# crown-face.net
KiCad netlist of a schematic drawn in EAGLE
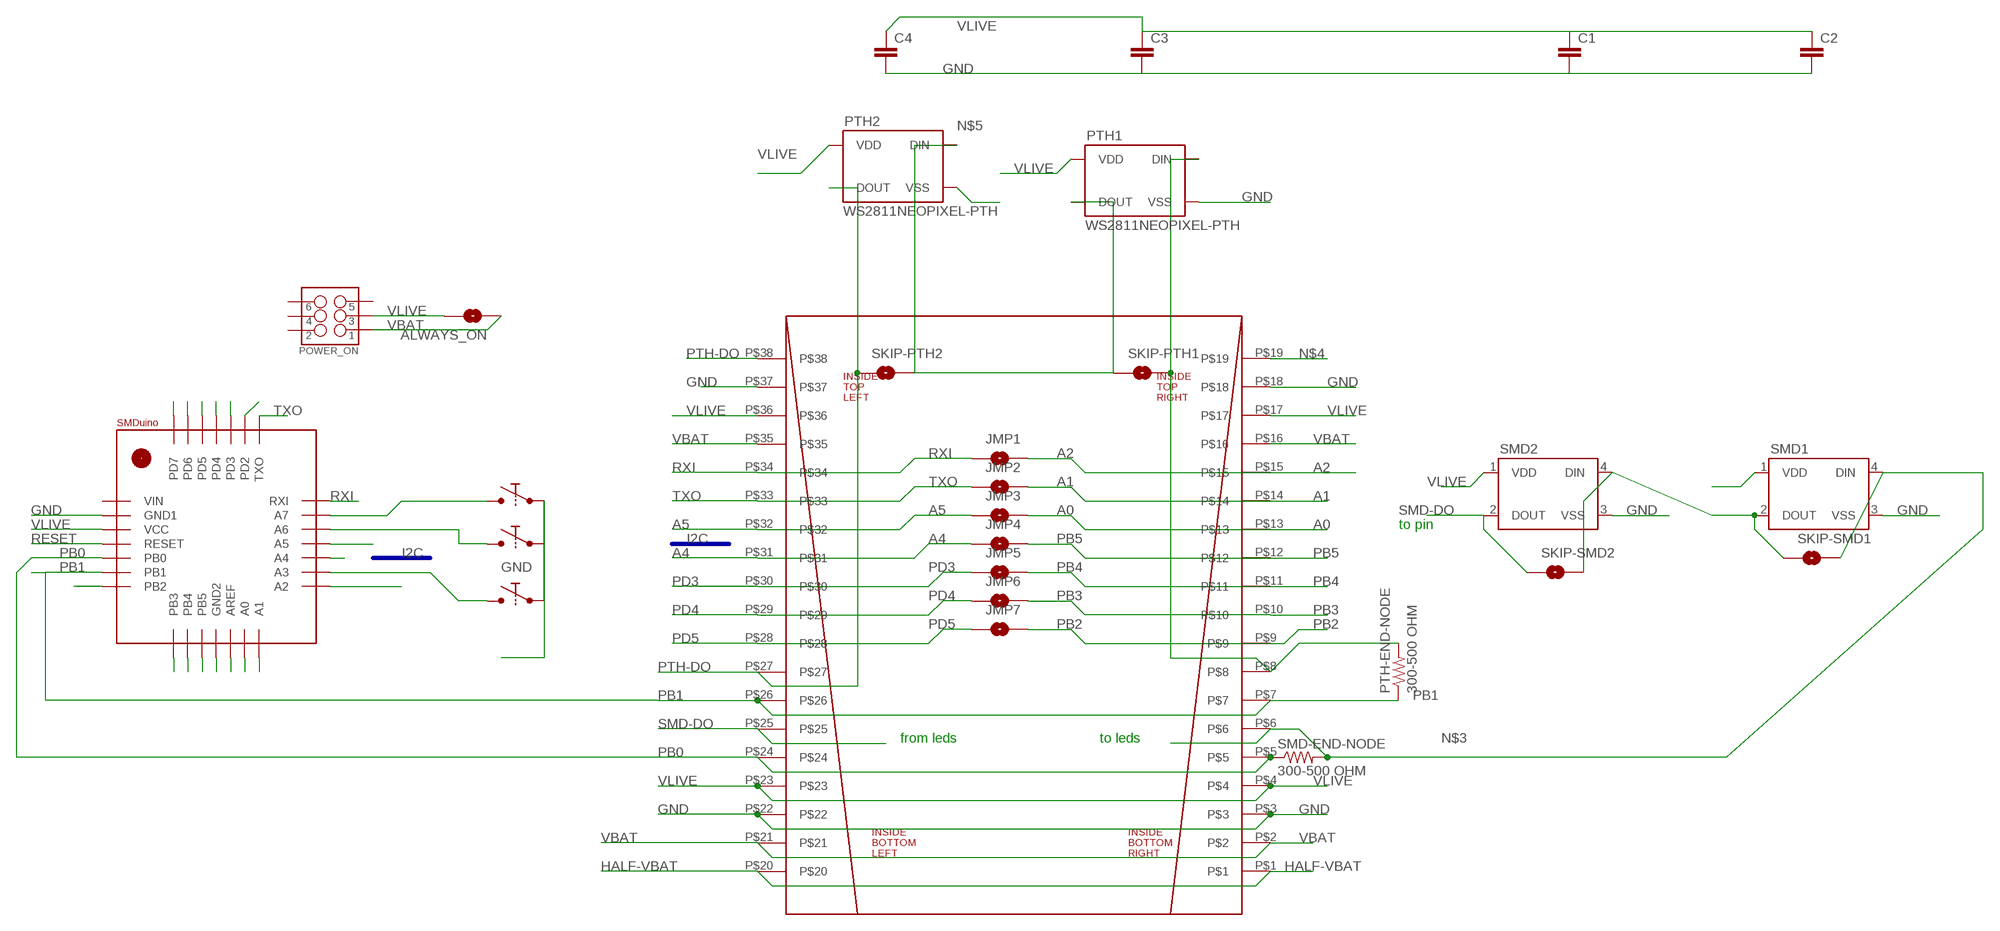
[diagram p0: schematic, sheet 1]

(export (version "E")
  (design (tool "Eeschema 10.0.6"))
  (components
    (comp (ref "A6")
      (value "BUTTONSMD_BUTTON")
      (footprint "eagle-import:SMD_BUTTON")
      (libsource (lib "eagle-import") (part "BUTTONSMD_BUTTON"))
    )
    (comp (ref "A7")
      (value "BUTTONSMD_BUTTON")
      (footprint "eagle-import:SMD_BUTTON")
      (libsource (lib "eagle-import") (part "BUTTONSMD_BUTTON"))
    )
    (comp (ref "ALWAYS_ON")
      (value "SOLDERJUMPERNC2")
      (footprint "eagle-import:SJ_2S-NOTRACE")
      (libsource (lib "eagle-import") (part "SOLDERJUMPERNC2"))
    )
    (comp (ref "C1")
      (value "CAP0805")
      (footprint "eagle-import:0805")
      (libsource (lib "eagle-import") (part "CAP0805"))
    )
    (comp (ref "C2")
      (value "CAP0805")
      (footprint "eagle-import:0805")
      (libsource (lib "eagle-import") (part "CAP0805"))
    )
    (comp (ref "C3")
      (value "CAP0805")
      (footprint "eagle-import:0805")
      (libsource (lib "eagle-import") (part "CAP0805"))
    )
    (comp (ref "C4")
      (value "CAP0805")
      (footprint "eagle-import:0805")
      (libsource (lib "eagle-import") (part "CAP0805"))
    )
    (comp (ref "D2")
      (value "BUTTONSMD_BUTTON")
      (footprint "eagle-import:SMD_BUTTON")
      (libsource (lib "eagle-import") (part "BUTTONSMD_BUTTON"))
    )
    (comp (ref "JMP1")
      (value "SOLDERJUMPERNC2")
      (footprint "eagle-import:SJ_2S-NOTRACE")
      (libsource (lib "eagle-import") (part "SOLDERJUMPERNC2"))
    )
    (comp (ref "JMP2")
      (value "SOLDERJUMPERNC2")
      (footprint "eagle-import:SJ_2S-NOTRACE")
      (libsource (lib "eagle-import") (part "SOLDERJUMPERNC2"))
    )
    (comp (ref "JMP3")
      (value "SOLDERJUMPERNC2")
      (footprint "eagle-import:SJ_2S-NOTRACE")
      (libsource (lib "eagle-import") (part "SOLDERJUMPERNC2"))
    )
    (comp (ref "JMP4")
      (value "SOLDERJUMPERNC2")
      (footprint "eagle-import:SJ_2S-NOTRACE")
      (libsource (lib "eagle-import") (part "SOLDERJUMPERNC2"))
    )
    (comp (ref "JMP5")
      (value "SOLDERJUMPERNC2")
      (footprint "eagle-import:SJ_2S-NOTRACE")
      (libsource (lib "eagle-import") (part "SOLDERJUMPERNC2"))
    )
    (comp (ref "JMP6")
      (value "SOLDERJUMPERNC2")
      (footprint "eagle-import:SJ_2S-NOTRACE")
      (libsource (lib "eagle-import") (part "SOLDERJUMPERNC2"))
    )
    (comp (ref "JMP7")
      (value "SOLDERJUMPERNC2")
      (footprint "eagle-import:SJ_2S-NOTRACE")
      (libsource (lib "eagle-import") (part "SOLDERJUMPERNC2"))
    )
    (comp (ref "POWER_ON")
      (value "M03X2FEMALE_SMD")
      (footprint "eagle-import:2X3_SMD")
      (libsource (lib "eagle-import") (part "M03X2FEMALE_SMD"))
    )
    (comp (ref "PTH-END-NODE")
      (value "300-500 OHM")
      (footprint "eagle-import:0805")
      (libsource (lib "eagle-import") (part "RESISTOR0805-RES"))
    )
    (comp (ref "PTH1")
      (value "WS2811NEOPIXEL-PTH")
      (footprint "eagle-import:WS2811-PTH-FLAT")
      (libsource (lib "eagle-import") (part "WS2811NEOPIXEL-PTH"))
    )
    (comp (ref "PTH2")
      (value "WS2811NEOPIXEL-PTH")
      (footprint "eagle-import:WS2811-PTH-FLAT")
      (libsource (lib "eagle-import") (part "WS2811NEOPIXEL-PTH"))
    )
    (comp (ref "SKIP-PTH1")
      (value "SOLDERJUMPERNC2")
      (footprint "eagle-import:SJ_2S-NOTRACE")
      (libsource (lib "eagle-import") (part "SOLDERJUMPERNC2"))
    )
    (comp (ref "SKIP-PTH2")
      (value "SOLDERJUMPERNC2")
      (footprint "eagle-import:SJ_2S-NOTRACE")
      (libsource (lib "eagle-import") (part "SOLDERJUMPERNC2"))
    )
    (comp (ref "SKIP-SMD1")
      (value "SOLDERJUMPERNC2")
      (footprint "eagle-import:SJ_2S-NOTRACE")
      (libsource (lib "eagle-import") (part "SOLDERJUMPERNC2"))
    )
    (comp (ref "SKIP-SMD2")
      (value "SOLDERJUMPERNC2")
      (footprint "eagle-import:SJ_2S-NOTRACE")
      (libsource (lib "eagle-import") (part "SOLDERJUMPERNC2"))
    )
    (comp (ref "SMD-END-NODE")
      (value "300-500 OHM")
      (footprint "eagle-import:0805")
      (libsource (lib "eagle-import") (part "RESISTOR0805-RES"))
    )
    (comp (ref "SMD1")
      (value "WS2812B")
      (footprint "eagle-import:WS2812B")
      (libsource (lib "eagle-import") (part "WS2812B"))
    )
    (comp (ref "SMD2")
      (value "WS2812B")
      (footprint "eagle-import:WS2812B")
      (libsource (lib "eagle-import") (part "WS2812B"))
    )
    (comp (ref "U$1")
      (value "SMDUINO")
      (footprint "eagle-import:SMDUINO")
      (libsource (lib "eagle-import") (part "SMDUINO"))
    )
    (comp (ref "U$2")
      (value "CROWNSTANDARD")
      (footprint "eagle-import:CROWN")
      (libsource (lib "eagle-import") (part "CROWNSTANDARD"))
    )
  )
  (nets
    (net (code "2") (name "/A0") (class "Default")
      (node (ref "JMP3") (pin "2") (pinfunction "2_2") (pintype "passive"))
      (node (ref "U$1") (pin "A0") (pinfunction "A0_A0") (pintype "bidirectional"))
      (node (ref "U$2") (pin "P$13") (pinfunction "P$13_P$13") (pintype "bidirectional"))
    )
    (net (code "3") (name "/A1") (class "Default")
      (node (ref "JMP2") (pin "2") (pinfunction "2_2") (pintype "passive"))
      (node (ref "U$1") (pin "A1") (pinfunction "A1_A1") (pintype "bidirectional"))
      (node (ref "U$2") (pin "P$14") (pinfunction "P$14_P$14") (pintype "bidirectional"))
    )
    (net (code "4") (name "/A2") (class "Default")
      (node (ref "JMP1") (pin "2") (pinfunction "2_2") (pintype "passive"))
      (node (ref "U$1") (pin "A2") (pinfunction "A2_A2") (pintype "bidirectional"))
      (node (ref "U$2") (pin "P$15") (pinfunction "P$15_P$15") (pintype "bidirectional"))
    )
    (net (code "5") (name "/A4") (class "Default")
      (node (ref "JMP4") (pin "1") (pinfunction "1_1") (pintype "passive"))
      (node (ref "U$1") (pin "A4") (pinfunction "A4_A4") (pintype "bidirectional"))
      (node (ref "U$2") (pin "P$31") (pinfunction "P$31_P$31") (pintype "bidirectional"))
    )
    (net (code "6") (name "/A5") (class "Default")
      (node (ref "JMP3") (pin "1") (pinfunction "1_1") (pintype "passive"))
      (node (ref "U$1") (pin "A5") (pinfunction "A5_A5") (pintype "bidirectional"))
      (node (ref "U$2") (pin "P$32") (pinfunction "P$32_P$32") (pintype "bidirectional"))
    )
    (net (code "7") (name "/GND") (class "Default")
      (node (ref "A6") (pin "P$3") (pinfunction "P$2_P$3") (pintype "bidirectional"))
      (node (ref "A6") (pin "P$4") (pinfunction "P$2_P$4") (pintype "bidirectional"))
      (node (ref "A7") (pin "P$3") (pinfunction "P$2_P$3") (pintype "bidirectional"))
      (node (ref "A7") (pin "P$4") (pinfunction "P$2_P$4") (pintype "bidirectional"))
      (node (ref "C1") (pin "2") (pinfunction "2_2") (pintype "passive"))
      (node (ref "C2") (pin "2") (pinfunction "2_2") (pintype "passive"))
      (node (ref "C3") (pin "2") (pinfunction "2_2") (pintype "passive"))
      (node (ref "C4") (pin "2") (pinfunction "2_2") (pintype "passive"))
      (node (ref "D2") (pin "P$3") (pinfunction "P$2_P$3") (pintype "bidirectional"))
      (node (ref "D2") (pin "P$4") (pinfunction "P$2_P$4") (pintype "bidirectional"))
      (node (ref "PTH1") (pin "P$2") (pinfunction "VSS_P$2") (pintype "power_in"))
      (node (ref "PTH1") (pin "P$6") (pinfunction "VSS_P$6") (pintype "power_in"))
      (node (ref "PTH2") (pin "P$2") (pinfunction "VSS_P$2") (pintype "power_in"))
      (node (ref "PTH2") (pin "P$6") (pinfunction "VSS_P$6") (pintype "power_in"))
      (node (ref "SMD1") (pin "3") (pinfunction "VSS_3") (pintype "power_in"))
      (node (ref "SMD2") (pin "3") (pinfunction "VSS_3") (pintype "power_in"))
      (node (ref "U$1") (pin "GND1") (pinfunction "GND1_GND1") (pintype "bidirectional"))
      (node (ref "U$2") (pin "P$18") (pinfunction "P$18_P$18") (pintype "bidirectional"))
      (node (ref "U$2") (pin "P$22") (pinfunction "P$22_P$22") (pintype "bidirectional"))
      (node (ref "U$2") (pin "P$3") (pinfunction "P$3_P$3") (pintype "bidirectional"))
      (node (ref "U$2") (pin "P$37") (pinfunction "P$37_P$37") (pintype "bidirectional"))
    )
    (net (code "8") (name "/HALF-VBAT") (class "Default")
      (node (ref "U$2") (pin "P$1") (pinfunction "P$1_P$1") (pintype "bidirectional"))
      (node (ref "U$2") (pin "P$20") (pinfunction "P$20_P$20") (pintype "bidirectional"))
    )
    (net (code "9") (name "/N$3") (class "Default")
      (node (ref "SKIP-SMD1") (pin "2") (pinfunction "2_2") (pintype "passive"))
      (node (ref "SMD-END-NODE") (pin "2") (pinfunction "2_2") (pintype "passive"))
      (node (ref "SMD1") (pin "4") (pinfunction "DIN_4") (pintype "input"))
      (node (ref "U$2") (pin "P$6") (pinfunction "P$6_P$6") (pintype "bidirectional"))
    )
    (net (code "10") (name "/N$4") (class "Default")
      (node (ref "PTH-END-NODE") (pin "2") (pinfunction "2_2") (pintype "passive"))
      (node (ref "PTH1") (pin "P$4") (pinfunction "DIN_P$4") (pintype "input"))
      (node (ref "PTH1") (pin "P$8") (pinfunction "DIN_P$8") (pintype "input"))
      (node (ref "SKIP-PTH1") (pin "2") (pinfunction "2_2") (pintype "passive"))
      (node (ref "U$2") (pin "P$19") (pinfunction "P$19_P$19") (pintype "bidirectional"))
      (node (ref "U$2") (pin "P$8") (pinfunction "P$8_P$8") (pintype "bidirectional"))
    )
    (net (code "11") (name "/N$5") (class "Default")
      (node (ref "PTH1") (pin "P$1") (pinfunction "DOUT_P$1") (pintype "output"))
      (node (ref "PTH1") (pin "P$5") (pinfunction "DOUT_P$5") (pintype "output"))
      (node (ref "PTH2") (pin "P$4") (pinfunction "DIN_P$4") (pintype "input"))
      (node (ref "PTH2") (pin "P$8") (pinfunction "DIN_P$8") (pintype "input"))
      (node (ref "SKIP-PTH1") (pin "1") (pinfunction "1_1") (pintype "passive"))
      (node (ref "SKIP-PTH2") (pin "2") (pinfunction "2_2") (pintype "passive"))
    )
    (net (code "12") (name "/PB0") (class "Default")
      (node (ref "SMD-END-NODE") (pin "1") (pinfunction "1_1") (pintype "passive"))
      (node (ref "U$1") (pin "PB0") (pinfunction "PB0_PB0") (pintype "bidirectional"))
      (node (ref "U$2") (pin "P$24") (pinfunction "P$24_P$24") (pintype "bidirectional"))
      (node (ref "U$2") (pin "P$5") (pinfunction "P$5_P$5") (pintype "bidirectional"))
    )
    (net (code "13") (name "/PB1") (class "Default")
      (node (ref "PTH-END-NODE") (pin "1") (pinfunction "1_1") (pintype "passive"))
      (node (ref "U$1") (pin "PB1") (pinfunction "PB1_PB1") (pintype "bidirectional"))
      (node (ref "U$2") (pin "P$26") (pinfunction "P$26_P$26") (pintype "bidirectional"))
      (node (ref "U$2") (pin "P$7") (pinfunction "P$7_P$7") (pintype "bidirectional"))
    )
    (net (code "14") (name "/PB2") (class "Default")
      (node (ref "JMP7") (pin "2") (pinfunction "2_2") (pintype "passive"))
      (node (ref "U$1") (pin "PB2") (pinfunction "PB2_PB2") (pintype "bidirectional"))
      (node (ref "U$2") (pin "P$9") (pinfunction "P$9_P$9") (pintype "bidirectional"))
    )
    (net (code "15") (name "/PB3") (class "Default")
      (node (ref "JMP6") (pin "2") (pinfunction "2_2") (pintype "passive"))
      (node (ref "U$1") (pin "PB3") (pinfunction "PB3_PB3") (pintype "bidirectional"))
      (node (ref "U$2") (pin "P$10") (pinfunction "P$10_P$10") (pintype "bidirectional"))
    )
    (net (code "16") (name "/PB4") (class "Default")
      (node (ref "JMP5") (pin "2") (pinfunction "2_2") (pintype "passive"))
      (node (ref "U$1") (pin "PB4") (pinfunction "PB4_PB4") (pintype "bidirectional"))
      (node (ref "U$2") (pin "P$11") (pinfunction "P$11_P$11") (pintype "bidirectional"))
    )
    (net (code "17") (name "/PB5") (class "Default")
      (node (ref "JMP4") (pin "2") (pinfunction "2_2") (pintype "passive"))
      (node (ref "U$1") (pin "PB5") (pinfunction "PB5_PB5") (pintype "bidirectional"))
      (node (ref "U$2") (pin "P$12") (pinfunction "P$12_P$12") (pintype "bidirectional"))
    )
    (net (code "18") (name "/PD3") (class "Default")
      (node (ref "JMP5") (pin "1") (pinfunction "1_1") (pintype "passive"))
      (node (ref "U$1") (pin "PD3") (pinfunction "PD3_PD3") (pintype "bidirectional"))
      (node (ref "U$2") (pin "P$30") (pinfunction "P$30_P$30") (pintype "bidirectional"))
    )
    (net (code "19") (name "/PD4") (class "Default")
      (node (ref "JMP6") (pin "1") (pinfunction "1_1") (pintype "passive"))
      (node (ref "U$1") (pin "PD4") (pinfunction "PD4_PD4") (pintype "bidirectional"))
      (node (ref "U$2") (pin "P$29") (pinfunction "P$29_P$29") (pintype "bidirectional"))
    )
    (net (code "20") (name "/PD5") (class "Default")
      (node (ref "JMP7") (pin "1") (pinfunction "1_1") (pintype "passive"))
      (node (ref "U$1") (pin "PD5") (pinfunction "PD5_PD5") (pintype "bidirectional"))
      (node (ref "U$2") (pin "P$28") (pinfunction "P$28_P$28") (pintype "bidirectional"))
    )
    (net (code "21") (name "/PTH-DO") (class "Default")
      (node (ref "PTH2") (pin "P$1") (pinfunction "DOUT_P$1") (pintype "output"))
      (node (ref "PTH2") (pin "P$5") (pinfunction "DOUT_P$5") (pintype "output"))
      (node (ref "SKIP-PTH2") (pin "1") (pinfunction "1_1") (pintype "passive"))
      (node (ref "U$2") (pin "P$27") (pinfunction "P$27_P$27") (pintype "bidirectional"))
      (node (ref "U$2") (pin "P$38") (pinfunction "P$38_P$38") (pintype "bidirectional"))
    )
    (net (code "22") (name "/RESET") (class "Default")
      (node (ref "U$1") (pin "RESET") (pinfunction "RESET_RESET") (pintype "bidirectional"))
    )
    (net (code "23") (name "/RXI") (class "Default")
      (node (ref "JMP1") (pin "1") (pinfunction "1_1") (pintype "passive"))
      (node (ref "U$1") (pin "RXI") (pinfunction "RXI_RXI") (pintype "bidirectional"))
      (node (ref "U$2") (pin "P$34") (pinfunction "P$34_P$34") (pintype "bidirectional"))
    )
    (net (code "24") (name "/SMD-DO") (class "Default")
      (node (ref "SKIP-SMD2") (pin "1") (pinfunction "1_1") (pintype "passive"))
      (node (ref "SMD2") (pin "2") (pinfunction "DOUT_2") (pintype "output"))
      (node (ref "U$2") (pin "P$25") (pinfunction "P$25_P$25") (pintype "bidirectional"))
    )
    (net (code "25") (name "/TXO") (class "Default")
      (node (ref "JMP2") (pin "1") (pinfunction "1_1") (pintype "passive"))
      (node (ref "U$1") (pin "TXO") (pinfunction "TXO_TXO") (pintype "bidirectional"))
      (node (ref "U$2") (pin "P$33") (pinfunction "P$33_P$33") (pintype "bidirectional"))
    )
    (net (code "26") (name "/VBAT") (class "Default")
      (node (ref "ALWAYS_ON") (pin "1") (pinfunction "1_1") (pintype "passive"))
      (node (ref "POWER_ON") (pin "1") (pinfunction "1_1") (pintype "bidirectional"))
      (node (ref "U$2") (pin "P$16") (pinfunction "P$16_P$16") (pintype "bidirectional"))
      (node (ref "U$2") (pin "P$2") (pinfunction "P$2_P$2") (pintype "bidirectional"))
      (node (ref "U$2") (pin "P$21") (pinfunction "P$21_P$21") (pintype "bidirectional"))
      (node (ref "U$2") (pin "P$35") (pinfunction "P$35_P$35") (pintype "bidirectional"))
    )
    (net (code "27") (name "/VLIVE") (class "Default")
      (node (ref "ALWAYS_ON") (pin "2") (pinfunction "2_2") (pintype "passive"))
      (node (ref "C1") (pin "1") (pinfunction "1_1") (pintype "passive"))
      (node (ref "C2") (pin "1") (pinfunction "1_1") (pintype "passive"))
      (node (ref "C3") (pin "1") (pinfunction "1_1") (pintype "passive"))
      (node (ref "C4") (pin "1") (pinfunction "1_1") (pintype "passive"))
      (node (ref "POWER_ON") (pin "3") (pinfunction "3_3") (pintype "bidirectional"))
      (node (ref "PTH1") (pin "P$3") (pinfunction "VDD_P$3") (pintype "power_in"))
      (node (ref "PTH1") (pin "P$7") (pinfunction "VDD_P$7") (pintype "power_in"))
      (node (ref "PTH2") (pin "P$3") (pinfunction "VDD_P$3") (pintype "power_in"))
      (node (ref "PTH2") (pin "P$7") (pinfunction "VDD_P$7") (pintype "power_in"))
      (node (ref "SMD1") (pin "1") (pinfunction "VDD_1") (pintype "power_in"))
      (node (ref "SMD2") (pin "1") (pinfunction "VDD_1") (pintype "power_in"))
      (node (ref "U$1") (pin "VCC") (pinfunction "VCC_VCC") (pintype "bidirectional"))
      (node (ref "U$2") (pin "P$17") (pinfunction "P$17_P$17") (pintype "bidirectional"))
      (node (ref "U$2") (pin "P$23") (pinfunction "P$23_P$23") (pintype "bidirectional"))
      (node (ref "U$2") (pin "P$36") (pinfunction "P$36_P$36") (pintype "bidirectional"))
      (node (ref "U$2") (pin "P$4") (pinfunction "P$4_P$4") (pintype "bidirectional"))
    )
    (net (code "29") (name "Net-(A6-P$1-PadP$2)") (class "Default")
      (node (ref "A6") (pin "P$1") (pinfunction "P$1_P$1") (pintype "bidirectional"))
      (node (ref "A6") (pin "P$2") (pinfunction "P$1_P$2") (pintype "bidirectional"))
      (node (ref "U$1") (pin "A3") (pinfunction "A3_A3") (pintype "bidirectional"))
    )
    (net (code "30") (name "Net-(A7-P$1-PadP$2)") (class "Default")
      (node (ref "A7") (pin "P$1") (pinfunction "P$1_P$1") (pintype "bidirectional"))
      (node (ref "A7") (pin "P$2") (pinfunction "P$1_P$2") (pintype "bidirectional"))
      (node (ref "U$1") (pin "A6") (pinfunction "A6_A6") (pintype "bidirectional"))
    )
    (net (code "31") (name "Net-(D2-P$1-PadP$2)") (class "Default")
      (node (ref "D2") (pin "P$1") (pinfunction "P$1_P$1") (pintype "bidirectional"))
      (node (ref "D2") (pin "P$2") (pinfunction "P$1_P$2") (pintype "bidirectional"))
      (node (ref "U$1") (pin "A7") (pinfunction "A7_A7") (pintype "bidirectional"))
    )
    (net (code "32") (name "Net-(SMD1-DOUT)") (class "Default")
      (node (ref "SKIP-SMD1") (pin "1") (pinfunction "1_1") (pintype "passive"))
      (node (ref "SKIP-SMD2") (pin "2") (pinfunction "2_2") (pintype "passive"))
      (node (ref "SMD1") (pin "2") (pinfunction "DOUT_2") (pintype "output"))
      (node (ref "SMD2") (pin "4") (pinfunction "DIN_4") (pintype "input"))
    )
    (net (code "33") (name "unconnected-(POWER_ON-Pad2)") (class "Default")
      (node (ref "POWER_ON") (pin "2") (pinfunction "2_2") (pintype "bidirectional"))
    )
    (net (code "34") (name "unconnected-(POWER_ON-Pad4)") (class "Default")
      (node (ref "POWER_ON") (pin "4") (pinfunction "4_4") (pintype "bidirectional"))
    )
    (net (code "35") (name "unconnected-(POWER_ON-Pad5)") (class "Default")
      (node (ref "POWER_ON") (pin "5") (pinfunction "5_5") (pintype "bidirectional"))
    )
    (net (code "36") (name "unconnected-(POWER_ON-Pad6)") (class "Default")
      (node (ref "POWER_ON") (pin "6") (pinfunction "6_6") (pintype "bidirectional"))
    )
    (net (code "37") (name "unconnected-(U$1-PadAREF)") (class "Default")
      (node (ref "U$1") (pin "AREF") (pinfunction "AREF_AREF") (pintype "bidirectional"))
    )
    (net (code "38") (name "unconnected-(U$1-PadGND2)") (class "Default")
      (node (ref "U$1") (pin "GND2") (pinfunction "GND2_GND2") (pintype "bidirectional"))
    )
    (net (code "39") (name "unconnected-(U$1-PadPD2)") (class "Default")
      (node (ref "U$1") (pin "PD2") (pinfunction "PD2_PD2") (pintype "bidirectional"))
    )
    (net (code "40") (name "unconnected-(U$1-PadPD6)") (class "Default")
      (node (ref "U$1") (pin "PD6") (pinfunction "PD6_PD6") (pintype "bidirectional"))
    )
    (net (code "41") (name "unconnected-(U$1-PadPD7)") (class "Default")
      (node (ref "U$1") (pin "PD7") (pinfunction "PD7_PD7") (pintype "bidirectional"))
    )
    (net (code "42") (name "unconnected-(U$1-PadVIN)") (class "Default")
      (node (ref "U$1") (pin "VIN") (pinfunction "VIN_VIN") (pintype "bidirectional"))
    )
  )
)
